# motor_driver.net
KiCad netlist of a schematic drawn in EAGLE
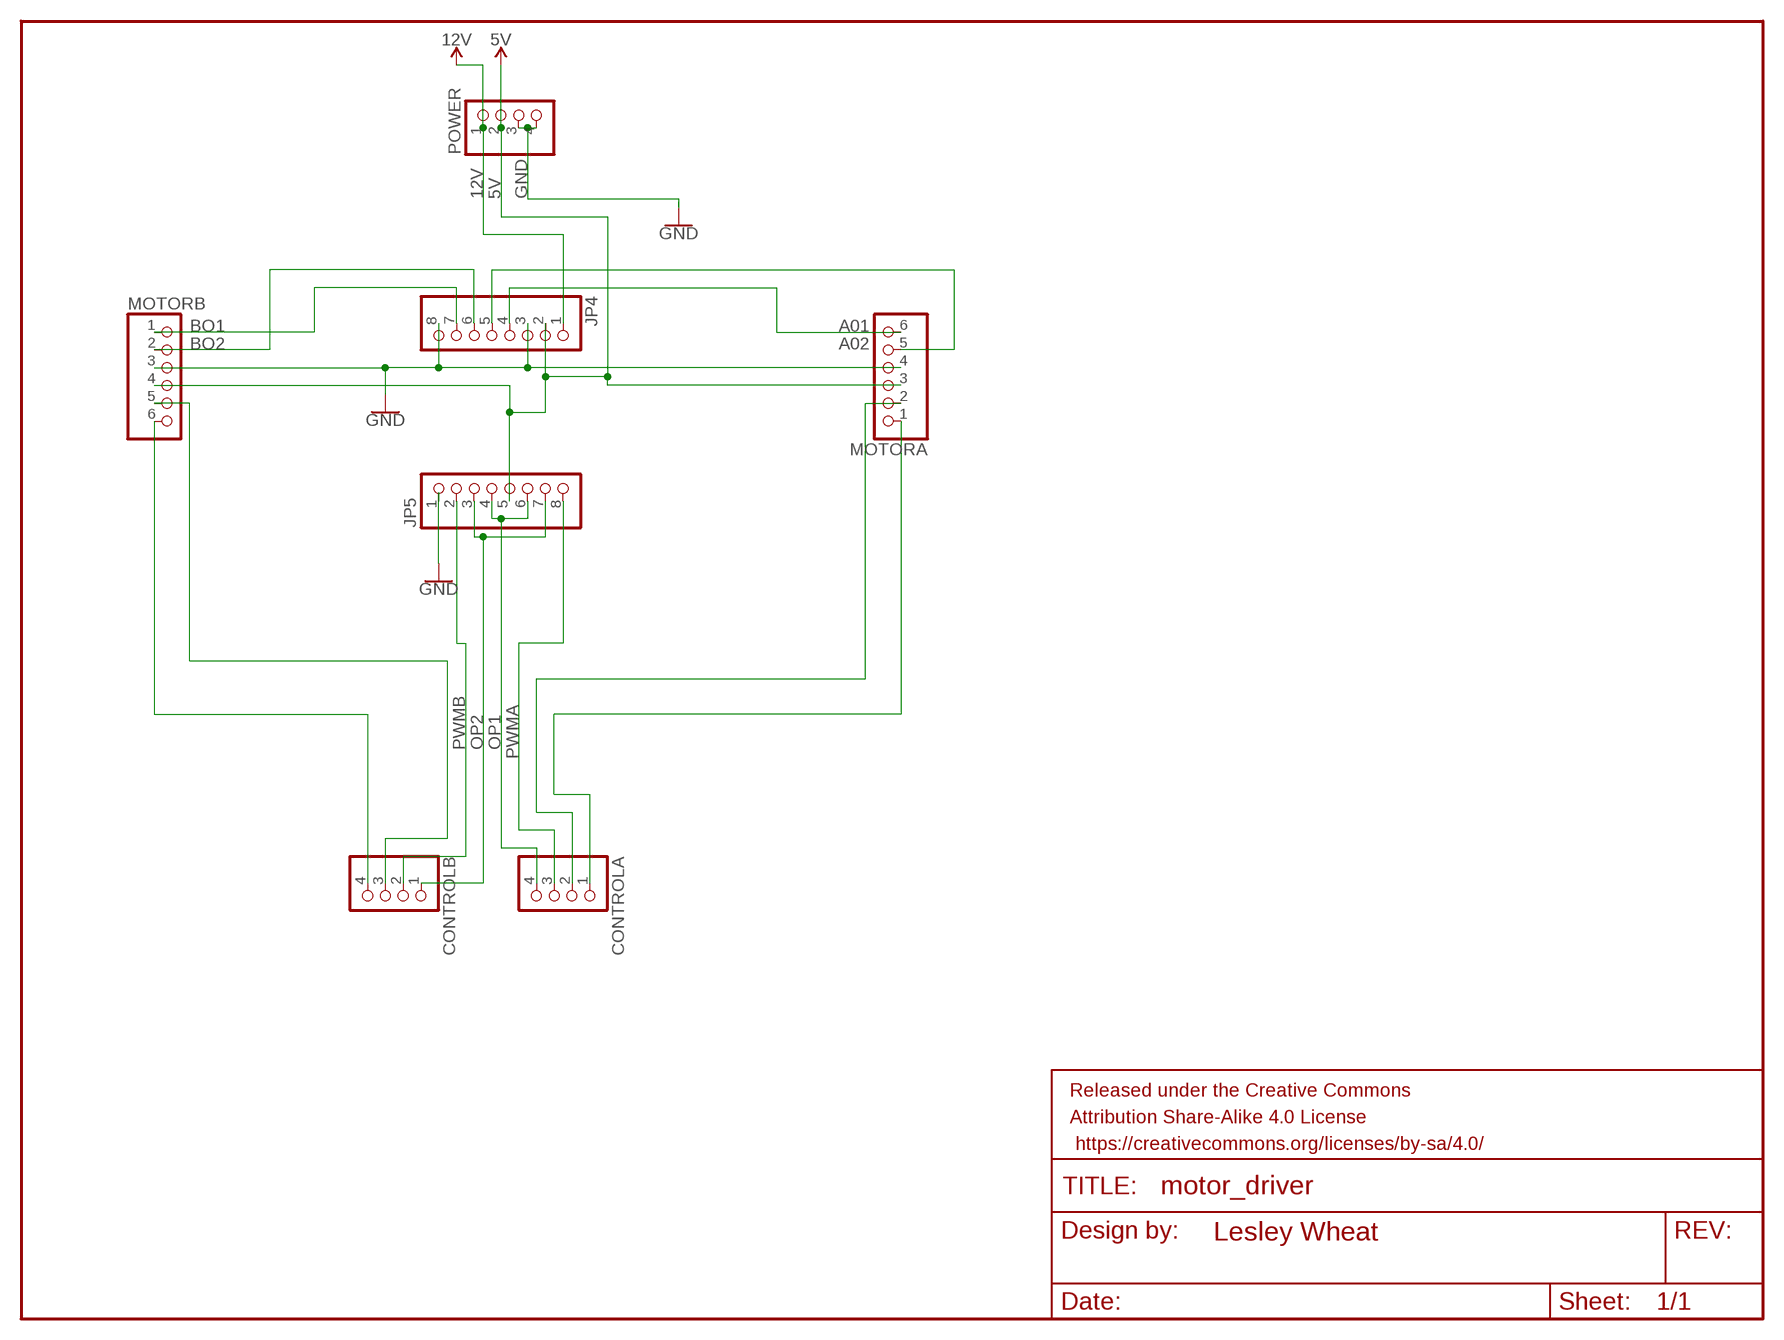
[diagram p0: schematic, sheet 1]

(export (version "E")
  (design (tool "Eeschema 10.0.6"))
  (components
    (comp (ref "CONTROLA")
      (value "PINHD-1X4")
      (footprint "eagle-import:1X04")
      (libsource (lib "eagle-import") (part "PINHD-1X4"))
    )
    (comp (ref "CONTROLB")
      (value "PINHD-1X4")
      (footprint "eagle-import:1X04")
      (libsource (lib "eagle-import") (part "PINHD-1X4"))
    )
    (comp (ref "FRAME2")
      (value "FRAME-LETTERNO_PACKAGE")
      (footprint "eagle-import:DUMMY")
      (fields (field (name "DESIGNER") "Lesley Wheat") (field (name "DESIGNER_1") "Lesley Wheat"))
      (libsource (lib "eagle-import") (part "FRAME-LETTERNO_PACKAGE"))
    )
    (comp (ref "JP4")
      (value "PINHD-1X8")
      (footprint "eagle-import:1X08")
      (libsource (lib "eagle-import") (part "PINHD-1X8"))
    )
    (comp (ref "JP5")
      (value "PINHD-1X8")
      (footprint "eagle-import:1X08")
      (libsource (lib "eagle-import") (part "PINHD-1X8"))
    )
    (comp (ref "MOTORA")
      (value "PINHD-1X6")
      (footprint "eagle-import:1X06")
      (libsource (lib "eagle-import") (part "PINHD-1X6"))
    )
    (comp (ref "MOTORB")
      (value "PINHD-1X6")
      (footprint "eagle-import:1X06")
      (libsource (lib "eagle-import") (part "PINHD-1X6"))
    )
    (comp (ref "POWER")
      (value "PINHD-1X4")
      (footprint "eagle-import:1X04")
      (libsource (lib "eagle-import") (part "PINHD-1X4"))
    )
  )
  (nets
    (net (code "1") (name "/A01") (class "Default")
      (node (ref "JP4") (pin "4") (pinfunction "4_4") (pintype "passive"))
      (node (ref "MOTORA") (pin "6") (pinfunction "6_6") (pintype "passive"))
    )
    (net (code "2") (name "/A02") (class "Default")
      (node (ref "JP4") (pin "5") (pinfunction "5_5") (pintype "passive"))
      (node (ref "MOTORA") (pin "5") (pinfunction "5_5") (pintype "passive"))
    )
    (net (code "3") (name "/BO1") (class "Default")
      (node (ref "JP4") (pin "7") (pinfunction "7_7") (pintype "passive"))
      (node (ref "MOTORB") (pin "1") (pinfunction "1_1") (pintype "passive"))
    )
    (net (code "4") (name "/BO2") (class "Default")
      (node (ref "JP4") (pin "6") (pinfunction "6_6") (pintype "passive"))
      (node (ref "MOTORB") (pin "2") (pinfunction "2_2") (pintype "passive"))
    )
    (net (code "5") (name "/OP1") (class "Default")
      (node (ref "CONTROLA") (pin "4") (pinfunction "4_4") (pintype "passive"))
      (node (ref "JP5") (pin "4") (pinfunction "4_4") (pintype "passive"))
      (node (ref "JP5") (pin "6") (pinfunction "6_6") (pintype "passive"))
    )
    (net (code "6") (name "/OP2") (class "Default")
      (node (ref "CONTROLB") (pin "1") (pinfunction "1_1") (pintype "passive"))
      (node (ref "JP5") (pin "3") (pinfunction "3_3") (pintype "passive"))
      (node (ref "JP5") (pin "7") (pinfunction "7_7") (pintype "passive"))
    )
    (net (code "7") (name "/PWMA") (class "Default")
      (node (ref "CONTROLA") (pin "3") (pinfunction "3_3") (pintype "passive"))
      (node (ref "JP5") (pin "8") (pinfunction "8_8") (pintype "passive"))
    )
    (net (code "8") (name "/PWMB") (class "Default")
      (node (ref "CONTROLB") (pin "2") (pinfunction "2_2") (pintype "passive"))
      (node (ref "JP5") (pin "2") (pinfunction "2_2") (pintype "passive"))
    )
    (net (code "9") (name "5V") (class "Default")
      (node (ref "JP4") (pin "2") (pinfunction "2_2") (pintype "passive"))
      (node (ref "JP5") (pin "5") (pinfunction "5_5") (pintype "passive"))
      (node (ref "MOTORA") (pin "3") (pinfunction "3_3") (pintype "passive"))
      (node (ref "MOTORB") (pin "4") (pinfunction "4_4") (pintype "passive"))
      (node (ref "POWER") (pin "2") (pinfunction "2_2") (pintype "passive"))
    )
    (net (code "10") (name "12V") (class "Default")
      (node (ref "JP4") (pin "1") (pinfunction "1_1") (pintype "passive"))
      (node (ref "POWER") (pin "1") (pinfunction "1_1") (pintype "passive"))
    )
    (net (code "11") (name "GND") (class "Default")
      (node (ref "JP4") (pin "3") (pinfunction "3_3") (pintype "passive"))
      (node (ref "JP4") (pin "8") (pinfunction "8_8") (pintype "passive"))
      (node (ref "JP5") (pin "1") (pinfunction "1_1") (pintype "passive"))
      (node (ref "MOTORA") (pin "4") (pinfunction "4_4") (pintype "passive"))
      (node (ref "MOTORB") (pin "3") (pinfunction "3_3") (pintype "passive"))
      (node (ref "POWER") (pin "3") (pinfunction "3_3") (pintype "passive"))
      (node (ref "POWER") (pin "4") (pinfunction "4_4") (pintype "passive"))
    )
    (net (code "12") (name "Net-(CONTROLA-Pad1)") (class "Default")
      (node (ref "CONTROLA") (pin "1") (pinfunction "1_1") (pintype "passive"))
      (node (ref "MOTORA") (pin "1") (pinfunction "1_1") (pintype "passive"))
    )
    (net (code "13") (name "Net-(CONTROLA-Pad2)") (class "Default")
      (node (ref "CONTROLA") (pin "2") (pinfunction "2_2") (pintype "passive"))
      (node (ref "MOTORA") (pin "2") (pinfunction "2_2") (pintype "passive"))
    )
    (net (code "14") (name "Net-(CONTROLB-Pad3)") (class "Default")
      (node (ref "CONTROLB") (pin "3") (pinfunction "3_3") (pintype "passive"))
      (node (ref "MOTORB") (pin "5") (pinfunction "5_5") (pintype "passive"))
    )
    (net (code "15") (name "Net-(CONTROLB-Pad4)") (class "Default")
      (node (ref "CONTROLB") (pin "4") (pinfunction "4_4") (pintype "passive"))
      (node (ref "MOTORB") (pin "6") (pinfunction "6_6") (pintype "passive"))
    )
  )
)
